# AD637.net
KiCad netlist of a schematic drawn in Altium Designer
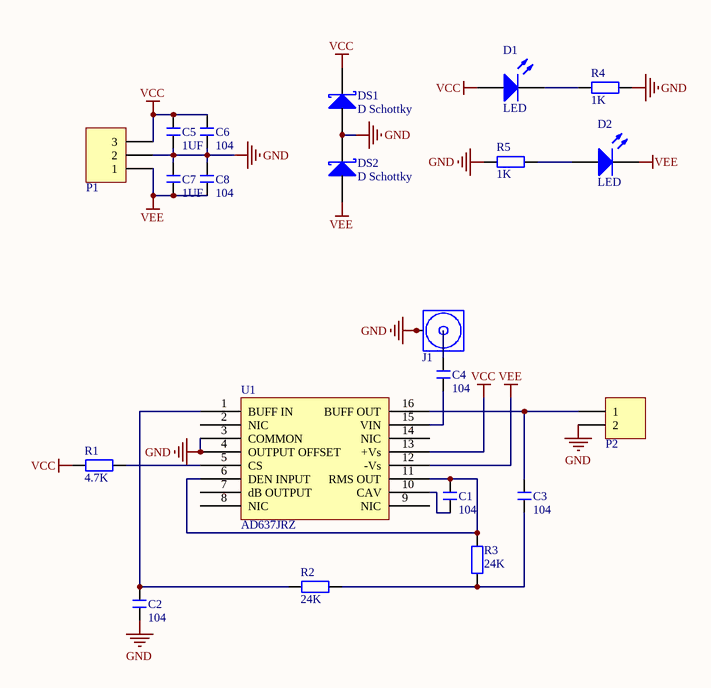
[diagram p0: AD637.SchDoc]

(export (version "E")
  (design (tool "Eeschema 10.0.6"))
  (components
    (comp (ref "C1")
      (value "104")
      (footprint "C 0805")
      (description "无极性贴片电容")
      (fields (field (name "版权归属") "源创客"))
      (libsource (lib "电阻-电容-电感") (part "C"))
    )
    (comp (ref "C2")
      (value "104")
      (footprint "C 1206")
      (description "无极性贴片电容")
      (fields (field (name "版权归属") "源创客"))
      (libsource (lib "电阻-电容-电感") (part "C"))
    )
    (comp (ref "C3")
      (value "104")
      (footprint "C 1206")
      (description "无极性贴片电容")
      (fields (field (name "版权归属") "源创客"))
      (libsource (lib "电阻-电容-电感") (part "C"))
    )
    (comp (ref "C4")
      (value "104")
      (footprint "C 0805")
      (description "无极性贴片电容")
      (fields (field (name "版权归属") "源创客"))
      (libsource (lib "电阻-电容-电感") (part "C"))
    )
    (comp (ref "C5")
      (value "1UF")
      (footprint "C 0805")
      (description "无极性贴片电容")
      (fields (field (name "版权归属") "源创客"))
      (libsource (lib "电阻-电容-电感") (part "C"))
    )
    (comp (ref "C6")
      (value "104")
      (footprint "C 0805")
      (description "无极性贴片电容")
      (fields (field (name "版权归属") "源创客"))
      (libsource (lib "电阻-电容-电感") (part "C"))
    )
    (comp (ref "C7")
      (value "1UF")
      (footprint "C 0805")
      (description "无极性贴片电容")
      (fields (field (name "版权归属") "源创客"))
      (libsource (lib "电阻-电容-电感") (part "C"))
    )
    (comp (ref "C8")
      (value "104")
      (footprint "C 0805")
      (description "无极性贴片电容")
      (fields (field (name "版权归属") "源创客"))
      (libsource (lib "电阻-电容-电感") (part "C"))
    )
    (comp (ref "D1")
      (value "LED")
      (footprint "LED_0805")
      (description "发光二极管")
      (fields (field (name "PUBLISHER") "Altium Limited"))
      (libsource (lib "LIB") (part "LED"))
    )
    (comp (ref "D2")
      (value "LED")
      (footprint "LED_0805")
      (description "发光二极管")
      (fields (field (name "PUBLISHER") "Altium Limited"))
      (libsource (lib "LIB") (part "LED"))
    )
    (comp (ref "DS1")
      (value "D Schottky")
      (footprint "DIODE-SMA")
      (description "Schottky Diode")
      (fields (field (name "PUBLISHER") "Altium Limited"))
      (libsource (lib "LIB") (part "D Schottky"))
    )
    (comp (ref "DS2")
      (value "D Schottky")
      (footprint "DIODE-SMA")
      (description "Schottky Diode")
      (fields (field (name "PUBLISHER") "Altium Limited"))
      (libsource (lib "LIB") (part "D Schottky"))
    )
    (comp (ref "J1") (value "COAX") (footprint "MCX5.08-5-H") (libsource (lib "LIB") (part "COAX")))
    (comp (ref "P1")
      (value "Header 3")
      (footprint "HDR3X1_B2")
      (description "接插件")
      (fields (field (name "PUBLISHER") "Altium Limited"))
      (libsource (lib "LIB") (part "Header 3"))
    )
    (comp (ref "P2")
      (value "Header 2")
      (footprint "HDR2X1_B2")
      (description "接插件")
      (fields (field (name "PUBLISHER") "Altium Limited"))
      (libsource (lib "LIB") (part "Header 2"))
    )
    (comp (ref "R1")
      (value "4.7K")
      (footprint "R 0603")
      (description "贴片电阻")
      (fields (field (name "版权归属") "源创客"))
      (libsource (lib "电阻-电容-电感") (part "R"))
    )
    (comp (ref "R2")
      (value "24K")
      (footprint "R 0603")
      (description "贴片电阻")
      (fields (field (name "版权归属") "源创客"))
      (libsource (lib "电阻-电容-电感") (part "R"))
    )
    (comp (ref "R3")
      (value "24K")
      (footprint "R 0603")
      (description "贴片电阻")
      (fields (field (name "版权归属") "源创客"))
      (libsource (lib "电阻-电容-电感") (part "R"))
    )
    (comp (ref "R4")
      (value "1K")
      (footprint "R 0805")
      (description "贴片电阻")
      (fields (field (name "版权归属") "源创客"))
      (libsource (lib "电阻-电容-电感") (part "R"))
    )
    (comp (ref "R5")
      (value "1K")
      (footprint "R 0805")
      (description "贴片电阻")
      (fields (field (name "版权归属") "源创客"))
      (libsource (lib "电阻-电容-电感") (part "R"))
    )
    (comp (ref "U1")
      (value "AD637JRZ")
      (footprint "RW_16_M")
      (description "High Precision, Wideband,RMS-to-DC Converter")
      (libsource (lib "LIB") (part "AD637JRZ"))
    )
  )
  (nets
    (net (code "1") (name "GND") (class "Default")
      (node (ref "C2") (pin "2") (pinfunction "2_2") (pintype "passive"))
      (node (ref "C5") (pin "2") (pinfunction "2_2") (pintype "passive"))
      (node (ref "C6") (pin "2") (pinfunction "2_2") (pintype "passive"))
      (node (ref "C7") (pin "1") (pinfunction "1_1") (pintype "passive"))
      (node (ref "C8") (pin "1") (pinfunction "1_1") (pintype "passive"))
      (node (ref "DS1") (pin "1") (pinfunction "1_1") (pintype "passive"))
      (node (ref "DS2") (pin "2") (pinfunction "2_2") (pintype "passive"))
      (node (ref "J1") (pin "2") (pinfunction "GND_2") (pintype "passive"))
      (node (ref "J1") (pin "3") (pinfunction "GND_3") (pintype "passive"))
      (node (ref "J1") (pin "4") (pinfunction "GND_4") (pintype "passive"))
      (node (ref "J1") (pin "5") (pinfunction "GND_5") (pintype "passive"))
      (node (ref "P1") (pin "2") (pinfunction "2_2") (pintype "passive"))
      (node (ref "P2") (pin "2") (pinfunction "2_2") (pintype "passive"))
      (node (ref "R4") (pin "2") (pinfunction "2_2") (pintype "passive"))
      (node (ref "R5") (pin "1") (pinfunction "1_1") (pintype "passive"))
      (node (ref "U1") (pin "3") (pinfunction "COMMON_3") (pintype "passive"))
      (node (ref "U1") (pin "4") (pinfunction "OUTPUT_OFFSET_4") (pintype "passive"))
    )
    (net (code "2") (name "Net-(C3-Pad2)") (class "Default")
      (node (ref "C3") (pin "2") (pinfunction "2_2") (pintype "passive"))
      (node (ref "R2") (pin "2") (pinfunction "2_2") (pintype "passive"))
      (node (ref "R3") (pin "1") (pinfunction "1_1") (pintype "passive"))
    )
    (net (code "3") (name "Net-(D1-K)") (class "Default")
      (node (ref "D1") (pin "2") (pinfunction "K_2") (pintype "passive"))
      (node (ref "R4") (pin "1") (pinfunction "1_1") (pintype "passive"))
    )
    (net (code "4") (name "Net-(D2-A)") (class "Default")
      (node (ref "D2") (pin "1") (pinfunction "A_1") (pintype "passive"))
      (node (ref "R5") (pin "2") (pinfunction "2_2") (pintype "passive"))
    )
    (net (code "5") (name "Net-(J1-Signal)") (class "Default")
      (node (ref "C4") (pin "1") (pinfunction "1_1") (pintype "passive"))
      (node (ref "J1") (pin "1") (pinfunction "Signal_1") (pintype "passive"))
    )
    (net (code "6") (name "Net-(U1-BUFF_IN)") (class "Default")
      (node (ref "C2") (pin "1") (pinfunction "1_1") (pintype "passive"))
      (node (ref "R2") (pin "1") (pinfunction "1_1") (pintype "passive"))
      (node (ref "U1") (pin "1") (pinfunction "BUFF_IN_1") (pintype "passive"))
    )
    (net (code "7") (name "Net-(U1-BUFF_OUT)") (class "Default")
      (node (ref "C3") (pin "1") (pinfunction "1_1") (pintype "passive"))
      (node (ref "P2") (pin "1") (pinfunction "1_1") (pintype "passive"))
      (node (ref "U1") (pin "16") (pinfunction "BUFF_OUT_16") (pintype "passive"))
    )
    (net (code "8") (name "Net-(U1-CAV)") (class "Default")
      (node (ref "C1") (pin "1") (pinfunction "1_1") (pintype "passive"))
      (node (ref "U1") (pin "10") (pinfunction "CAV_10") (pintype "passive"))
    )
    (net (code "9") (name "Net-(U1-CS)") (class "Default")
      (node (ref "R1") (pin "2") (pinfunction "2_2") (pintype "passive"))
      (node (ref "U1") (pin "5") (pinfunction "CS_5") (pintype "passive"))
    )
    (net (code "10") (name "Net-(U1-DEN_INPUT)") (class "Default")
      (node (ref "C1") (pin "2") (pinfunction "2_2") (pintype "passive"))
      (node (ref "R3") (pin "2") (pinfunction "2_2") (pintype "passive"))
      (node (ref "U1") (pin "11") (pinfunction "RMS_OUT_11") (pintype "passive"))
      (node (ref "U1") (pin "6") (pinfunction "DEN_INPUT_6") (pintype "passive"))
    )
    (net (code "11") (name "Net-(U1-VIN)") (class "Default")
      (node (ref "C4") (pin "2") (pinfunction "2_2") (pintype "passive"))
      (node (ref "U1") (pin "15") (pinfunction "VIN_15") (pintype "passive"))
    )
    (net (code "12") (name "VCC") (class "Default")
      (node (ref "C5") (pin "1") (pinfunction "1_1") (pintype "passive"))
      (node (ref "C6") (pin "1") (pinfunction "1_1") (pintype "passive"))
      (node (ref "D1") (pin "1") (pinfunction "A_1") (pintype "passive"))
      (node (ref "DS1") (pin "2") (pinfunction "2_2") (pintype "passive"))
      (node (ref "P1") (pin "3") (pinfunction "3_3") (pintype "passive"))
      (node (ref "R1") (pin "1") (pinfunction "1_1") (pintype "passive"))
      (node (ref "U1") (pin "13") (pinfunction "+Vs_13") (pintype "passive"))
    )
    (net (code "13") (name "VEE") (class "Default")
      (node (ref "C7") (pin "2") (pinfunction "2_2") (pintype "passive"))
      (node (ref "C8") (pin "2") (pinfunction "2_2") (pintype "passive"))
      (node (ref "D2") (pin "2") (pinfunction "K_2") (pintype "passive"))
      (node (ref "DS2") (pin "1") (pinfunction "1_1") (pintype "passive"))
      (node (ref "P1") (pin "1") (pinfunction "1_1") (pintype "passive"))
      (node (ref "U1") (pin "12") (pinfunction "-Vs_12") (pintype "passive"))
    )
    (net (code "14") (name "unconnected-(U1-NIC-Pad2)") (class "Default")
      (node (ref "U1") (pin "2") (pinfunction "NIC_2") (pintype "passive"))
    )
    (net (code "15") (name "unconnected-(U1-NIC-Pad8)") (class "Default")
      (node (ref "U1") (pin "8") (pinfunction "NIC_8") (pintype "passive"))
    )
    (net (code "16") (name "unconnected-(U1-NIC-Pad9)") (class "Default")
      (node (ref "U1") (pin "9") (pinfunction "NIC_9") (pintype "passive"))
    )
    (net (code "17") (name "unconnected-(U1-NIC-Pad14)") (class "Default")
      (node (ref "U1") (pin "14") (pinfunction "NIC_14") (pintype "passive"))
    )
    (net (code "18") (name "unconnected-(U1-dB_OUTPUT-Pad7)") (class "Default")
      (node (ref "U1") (pin "7") (pinfunction "dB_OUTPUT_7") (pintype "passive"))
    )
  )
)
